# EEZ_DIB_AUX_PS_r3B2.net
KiCad netlist of a schematic drawn in EAGLE
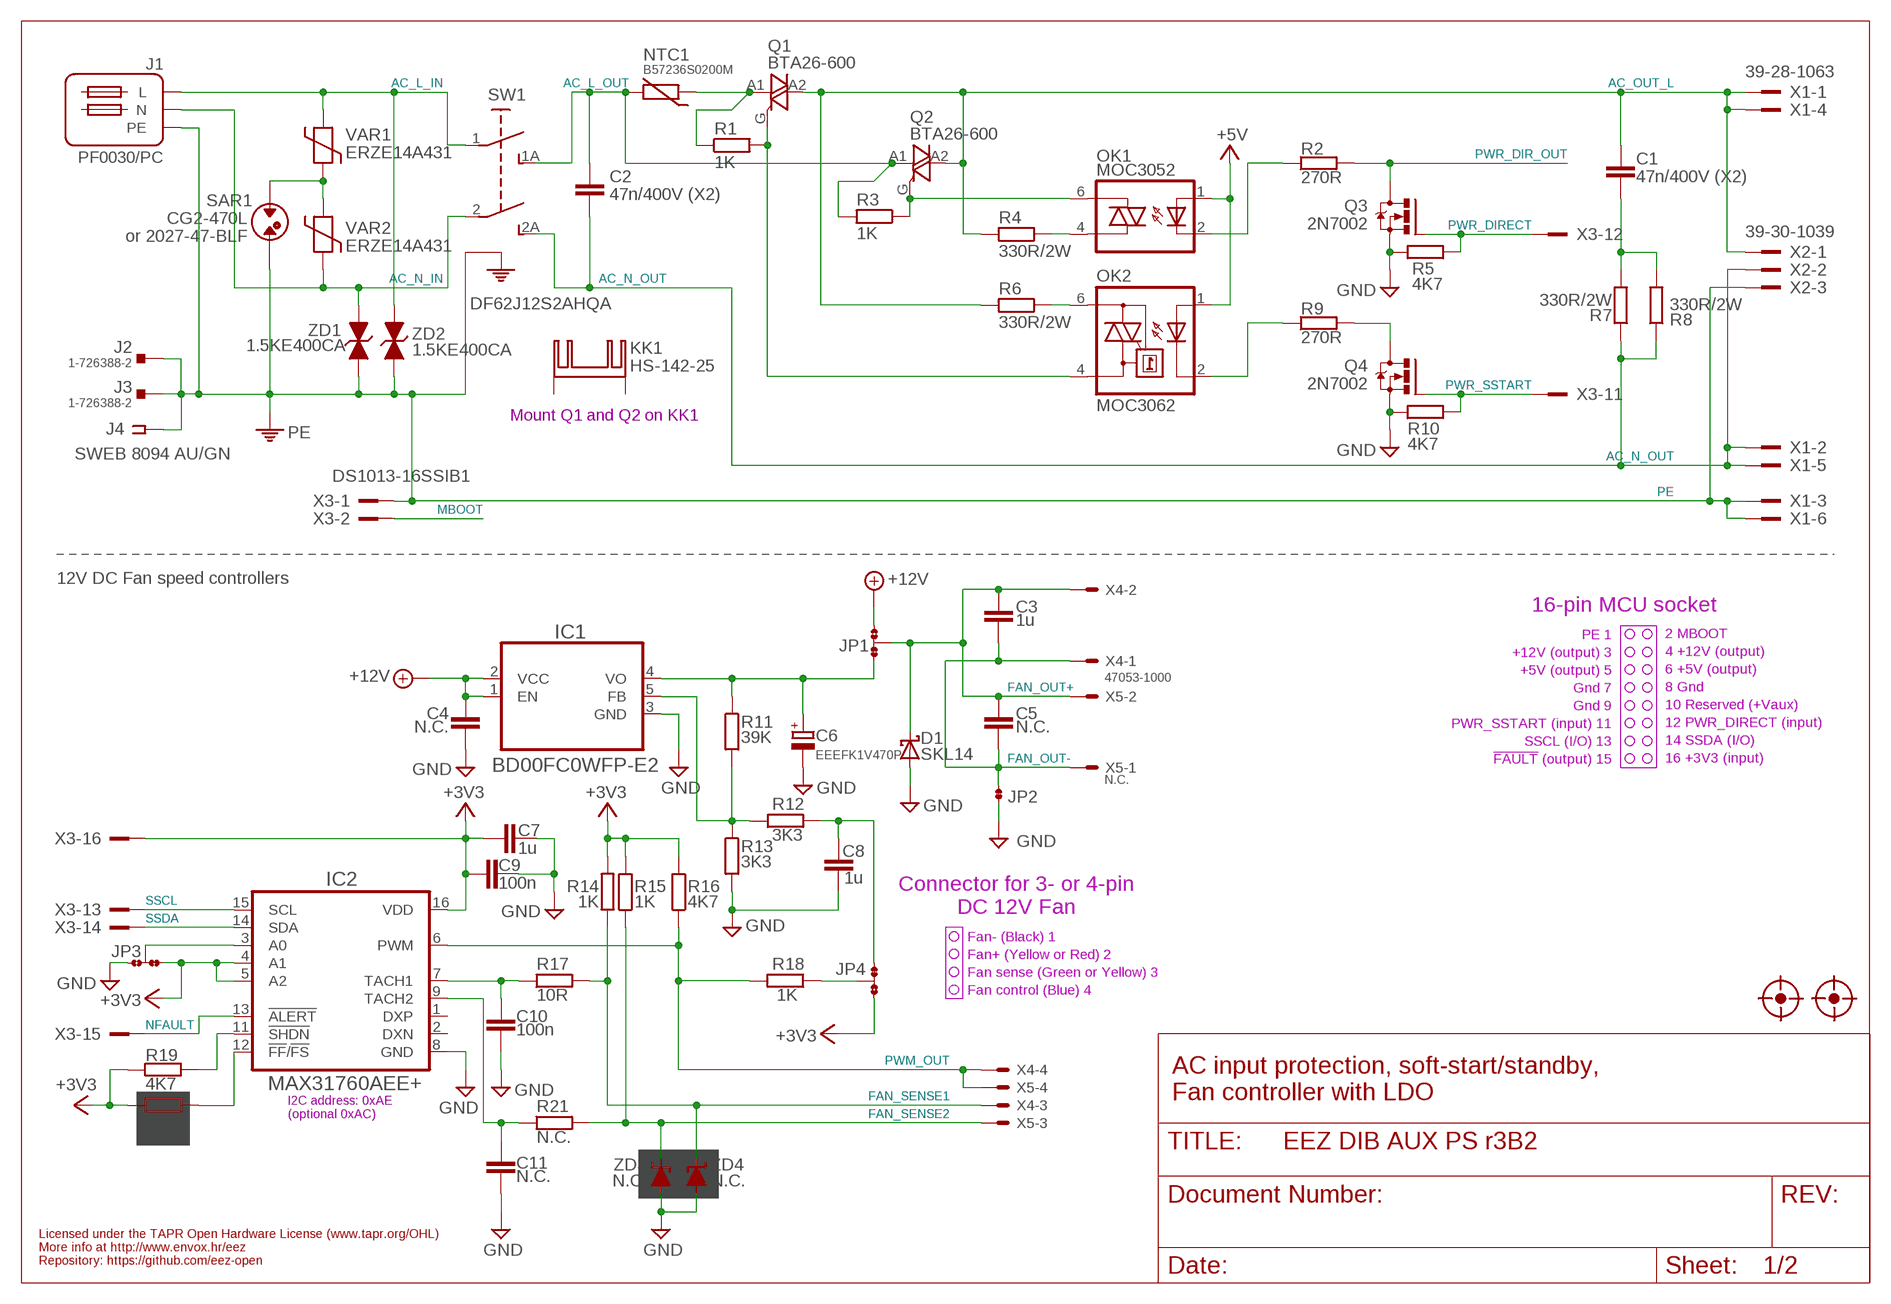
[diagram p0: schematic, sheet 1]
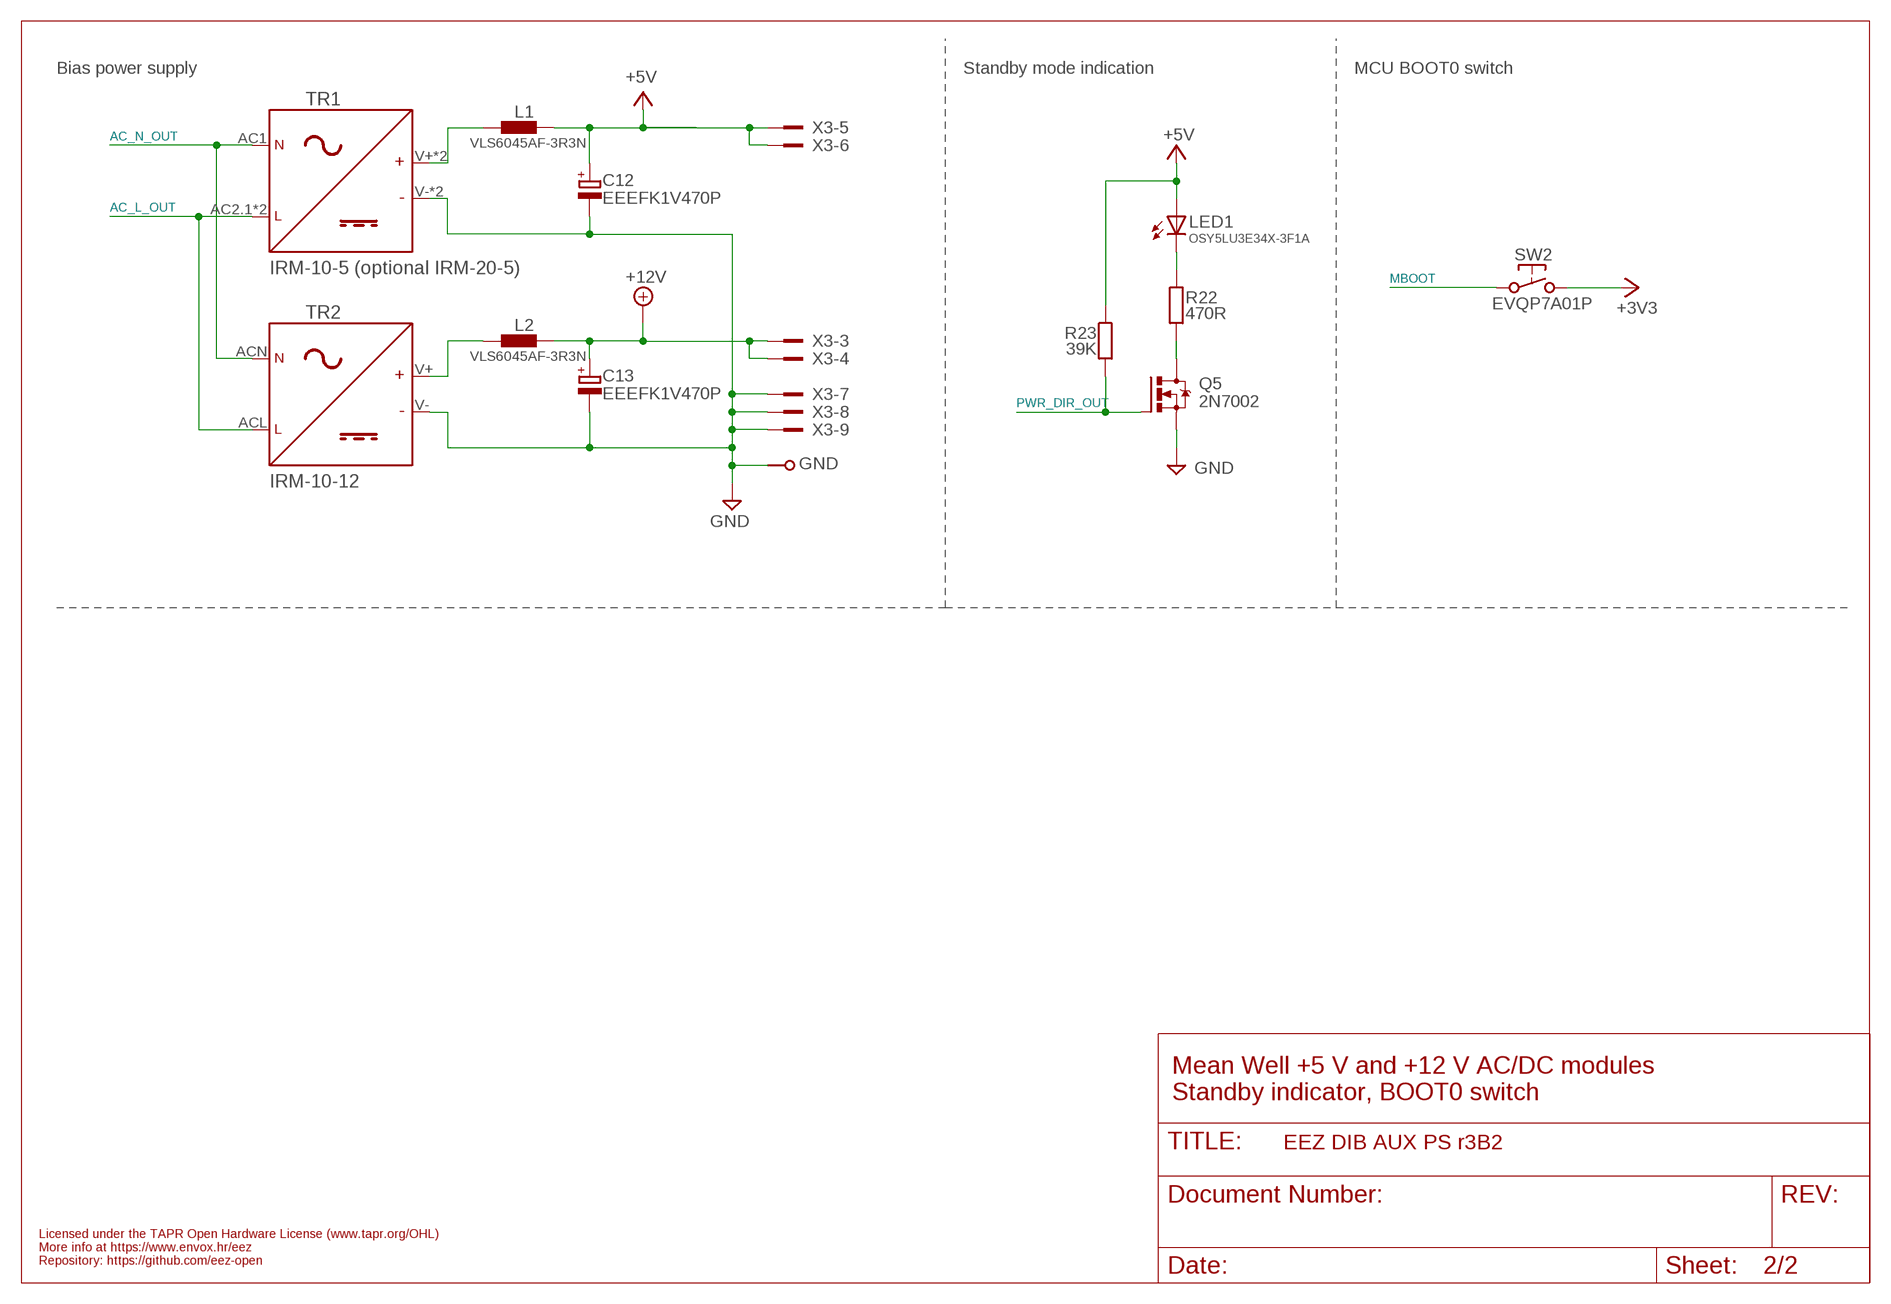
[diagram p1: schematic, sheet 2]

(export (version "E")
  (design (tool "Eeschema 10.0.6"))
  (components
    (comp (ref "C12")
      (value "EEEFK1V470P")
      (footprint "eagle-import:CAPAE660X610N")
      (libsource (lib "eagle-import") (part "ECAPPANASONIC_H"))
    )
    (comp (ref "C13")
      (value "EEEFK1V470P")
      (footprint "eagle-import:CAPAE660X610N")
      (libsource (lib "eagle-import") (part "ECAPPANASONIC_H"))
    )
    (comp (ref "GND")
      (value "PCB_TEST_TABSHIELD")
      (footprint "eagle-import:PCB_SHIELD_TAB")
      (libsource (lib "eagle-import") (part "PCB_TEST_TABSHIELD"))
    )
    (comp (ref "L1")
      (value "VLS6045AF-3R3N")
      (footprint "eagle-import:COILCRAFT_HPI0630")
      (libsource (lib "eagle-import") (part "COILCRAFT_HPI0630"))
    )
    (comp (ref "L2")
      (value "VLS6045AF-3R3N")
      (footprint "eagle-import:COILCRAFT_HPI0630")
      (libsource (lib "eagle-import") (part "COILCRAFT_HPI0630"))
    )
    (comp (ref "LED1")
      (value "OSY5LU3E34X-3F1A")
      (footprint "eagle-import:OSG8")
      (libsource (lib "eagle-import") (part "LEDOSG8"))
    )
    (comp (ref "Q5")
      (value "2N7002")
      (footprint "eagle-import:SOT103P240X110-3N")
      (fields
        (field (name "MPN") "2N7002-7-F")
        (field (name "MPN_1") "2N7002-7-F")
        (field (name "OC_FARNELL") "1713823")
        (field (name "OC_NEWARK") "25R5679")
        (field (name "PACKAGE") "SOT-23-3")
        (field (name "SUPPLIER") "DIODES INC.")
      )
      (libsource (lib "eagle-import") (part "2N7002"))
    )
    (comp (ref "R22")
      (value "470R")
      (footprint "eagle-import:R0805")
      (libsource (lib "eagle-import") (part "R-EU_R0805"))
    )
    (comp (ref "R23")
      (value "39K")
      (footprint "eagle-import:R0805")
      (libsource (lib "eagle-import") (part "R-EU_R0805"))
    )
    (comp (ref "SW2")
      (value "EVQP7A01P")
      (footprint "eagle-import:PANASONIC_EVQP")
      (libsource (lib "eagle-import") (part "EVQP7A01P"))
    )
    (comp (ref "TR1")
      (value "IRM-10-5 (optional IRM-20-5)")
      (footprint "eagle-import:IRM-10_20_COMBO")
      (libsource (lib "eagle-import") (part "AC_DC_ADAPTERIRM10/20"))
    )
    (comp (ref "TR2")
      (value "IRM-10-12")
      (footprint "eagle-import:IRM-10")
      (libsource (lib "eagle-import") (part "AC_DC_ADAPTERIRM10"))
    )
    (comp (ref "X3")
      (value "DS1013-16SSIB1")
      (footprint "eagle-import:IDC-16PIN")
      (libsource (lib "eagle-import") (part "IDC-16PIN"))
    )
    (comp (ref "C1")
      (value "47n/400V (X2)")
      (footprint "eagle-import:C102-054X133")
      (libsource (lib "eagle-import") (part "C-EU102-054X133"))
    )
    (comp (ref "C2")
      (value "47n/400V (X2)")
      (footprint "eagle-import:C102-054X133")
      (libsource (lib "eagle-import") (part "C-EU102-054X133"))
    )
    (comp (ref "C3")
      (value "1u")
      (footprint "eagle-import:C0805")
      (libsource (lib "eagle-import") (part "C-EUC0805"))
    )
    (comp (ref "C4")
      (value "N.C.")
      (footprint "eagle-import:C0805")
      (libsource (lib "eagle-import") (part "C-EUC0805"))
    )
    (comp (ref "C5")
      (value "N.C.")
      (footprint "eagle-import:C0805")
      (libsource (lib "eagle-import") (part "C-EUC0805"))
    )
    (comp (ref "C6")
      (value "EEEFK1V470P")
      (footprint "eagle-import:CAPAE660X610N")
      (libsource (lib "eagle-import") (part "ECAPPANASONIC_H"))
    )
    (comp (ref "C7")
      (value "1u")
      (footprint "eagle-import:C0805")
      (libsource (lib "eagle-import") (part "C-EUC0805"))
    )
    (comp (ref "C8")
      (value "1u")
      (footprint "eagle-import:C0805")
      (libsource (lib "eagle-import") (part "C-EUC0805"))
    )
    (comp (ref "C9")
      (value "100n")
      (footprint "eagle-import:C0603")
      (libsource (lib "eagle-import") (part "C-EUC0603"))
    )
    (comp (ref "C10")
      (value "100n")
      (footprint "eagle-import:C0603")
      (libsource (lib "eagle-import") (part "C-EUC0603"))
    )
    (comp (ref "C11")
      (value "N.C.")
      (footprint "eagle-import:C0603")
      (libsource (lib "eagle-import") (part "C-EUC0603"))
    )
    (comp (ref "D1")
      (value "SKL14")
      (footprint "eagle-import:SOD123")
      (libsource (lib "eagle-import") (part "SCHOTTKYSOD123"))
    )
    (comp (ref "FM1")
      (value "FIDUCIAL")
      (footprint "eagle-import:FIDUCIAL")
      (libsource (lib "eagle-import") (part "FIDUCIAL"))
    )
    (comp (ref "FM2")
      (value "FIDUCIAL")
      (footprint "eagle-import:FIDUCIAL")
      (libsource (lib "eagle-import") (part "FIDUCIAL"))
    )
    (comp (ref "IC1")
      (value "BD00FC0WFP-E2")
      (footprint "eagle-import:TO-252-5")
      (libsource (lib "eagle-import") (part "BD00FC0W"))
    )
    (comp (ref "IC2")
      (value "MAX31760AEE+")
      (footprint "eagle-import:DBQ16")
      (libsource (lib "eagle-import") (part "MAX31760AEE+"))
    )
    (comp (ref "J1")
      (value "PF0030/PC")
      (footprint "eagle-import:PF0030_PC")
      (libsource (lib "eagle-import") (part "PF0030/PC"))
    )
    (comp (ref "J2")
      (value "1-726388-2")
      (footprint "eagle-import:PCB_TAB-4.8MM")
      (libsource (lib "eagle-import") (part "PCB_TAB4.8MM"))
    )
    (comp (ref "J3")
      (value "1-726388-2")
      (footprint "eagle-import:PCB_TAB-4.8MM")
      (libsource (lib "eagle-import") (part "PCB_TAB4.8MM"))
    )
    (comp (ref "J4")
      (value "SWEB 8094 AU/GN")
      (footprint "eagle-import:S16N-PC")
      (libsource (lib "eagle-import") (part "BINDING_POSTCLIFF"))
    )
    (comp (ref "JP1")
      (value "JP3-CUT")
      (footprint "eagle-import:JP3-CUT")
      (libsource (lib "eagle-import") (part "JP3-CUT"))
    )
    (comp (ref "JP2")
      (value "JP2-NOCUT")
      (footprint "eagle-import:JP2-NOCUT")
      (libsource (lib "eagle-import") (part "JP2-NOCUT"))
    )
    (comp (ref "JP3")
      (value "JP3-CUT")
      (footprint "eagle-import:JP3-CUT")
      (libsource (lib "eagle-import") (part "JP3-CUT"))
    )
    (comp (ref "JP4")
      (value "JP3-CUT")
      (footprint "eagle-import:JP3-CUT")
      (libsource (lib "eagle-import") (part "JP3-CUT"))
    )
    (comp (ref "KK1")
      (value "HS-142-25")
      (footprint "eagle-import:SK129")
      (libsource (lib "eagle-import") (part "SK129-PAD"))
    )
    (comp (ref "NTC1")
      (value "B57236S0200M")
      (footprint "eagle-import:NTC_11.5X6_RM5")
      (libsource (lib "eagle-import") (part "NTC11.5X6"))
    )
    (comp (ref "OK1")
      (value "MOC3052")
      (footprint "eagle-import:DIL6-SMD")
      (libsource (lib "eagle-import") (part "MOC305X"))
    )
    (comp (ref "OK2")
      (value "MOC3062")
      (footprint "eagle-import:DIL6-SMD")
      (fields
        (field (name "MF") "FAIRCHILD SEMICONDUCTOR")
        (field (name "MPN") "MOC3033S-M")
        (field (name "MF_1") "FAIRCHILD SEMICONDUCTOR")
        (field (name "MPN_1") "MOC3033S-M")
        (field (name "OC_FARNELL") "unknown")
        (field (name "OC_NEWARK") "05C2878")
      )
      (libsource (lib "eagle-import") (part "MOC30S33"))
    )
    (comp (ref "Q1")
      (value "BTA26-600")
      (footprint "eagle-import:TOP3S-1")
      (libsource (lib "eagle-import") (part "BTA26-V"))
    )
    (comp (ref "Q2")
      (value "BTA26-600")
      (footprint "eagle-import:TOP3S-1")
      (libsource (lib "eagle-import") (part "BTA26-V"))
    )
    (comp (ref "Q3")
      (value "2N7002")
      (footprint "eagle-import:SOT103P240X110-3N")
      (fields (field (name "MPN") "2N7002-7-F"))
      (libsource (lib "eagle-import") (part "2N7002"))
    )
    (comp (ref "Q4")
      (value "2N7002")
      (footprint "eagle-import:SOT103P240X110-3N")
      (fields (field (name "MPN") "2N7002-7-F"))
      (libsource (lib "eagle-import") (part "2N7002"))
    )
    (comp (ref "R1")
      (value "1K")
      (footprint "eagle-import:R0805")
      (libsource (lib "eagle-import") (part "R-EU_R0805"))
    )
    (comp (ref "R2")
      (value "270R")
      (footprint "eagle-import:R0805")
      (libsource (lib "eagle-import") (part "R-EU_R0805"))
    )
    (comp (ref "R3")
      (value "1K")
      (footprint "eagle-import:R0805")
      (libsource (lib "eagle-import") (part "R-EU_R0805"))
    )
    (comp (ref "R4")
      (value "330R/2W")
      (footprint "eagle-import:R2512")
      (libsource (lib "eagle-import") (part "R-EU_R2512"))
    )
    (comp (ref "R5")
      (value "4K7")
      (footprint "eagle-import:R0805")
      (libsource (lib "eagle-import") (part "R-EU_R0805"))
    )
    (comp (ref "R6")
      (value "330R/2W")
      (footprint "eagle-import:R2512")
      (libsource (lib "eagle-import") (part "R-EU_R2512"))
    )
    (comp (ref "R7")
      (value "330R/2W")
      (footprint "eagle-import:R2512")
      (libsource (lib "eagle-import") (part "R-EU_R2512"))
    )
    (comp (ref "R8")
      (value "330R/2W")
      (footprint "eagle-import:R2512")
      (libsource (lib "eagle-import") (part "R-EU_R2512"))
    )
    (comp (ref "R9")
      (value "270R")
      (footprint "eagle-import:R0805")
      (libsource (lib "eagle-import") (part "R-EU_R0805"))
    )
    (comp (ref "R10")
      (value "4K7")
      (footprint "eagle-import:R0805")
      (libsource (lib "eagle-import") (part "R-EU_R0805"))
    )
    (comp (ref "R11")
      (value "39K")
      (footprint "eagle-import:R0805")
      (libsource (lib "eagle-import") (part "R-EU_R0805"))
    )
    (comp (ref "R12")
      (value "3K3")
      (footprint "eagle-import:R0805")
      (libsource (lib "eagle-import") (part "R-EU_R0805"))
    )
    (comp (ref "R13")
      (value "3K3")
      (footprint "eagle-import:R0805")
      (libsource (lib "eagle-import") (part "R-EU_R0805"))
    )
    (comp (ref "R14")
      (value "1K")
      (footprint "eagle-import:R0805")
      (libsource (lib "eagle-import") (part "R-EU_R0805"))
    )
    (comp (ref "R15")
      (value "1K")
      (footprint "eagle-import:R0805")
      (libsource (lib "eagle-import") (part "R-EU_R0805"))
    )
    (comp (ref "R16")
      (value "4K7")
      (footprint "eagle-import:R0805")
      (libsource (lib "eagle-import") (part "R-EU_R0805"))
    )
    (comp (ref "R17")
      (value "10R")
      (footprint "eagle-import:R0805")
      (libsource (lib "eagle-import") (part "R-EU_R0805"))
    )
    (comp (ref "R18")
      (value "1K")
      (footprint "eagle-import:R0805")
      (libsource (lib "eagle-import") (part "R-EU_R0805"))
    )
    (comp (ref "R19")
      (value "4K7")
      (footprint "eagle-import:R0805")
      (libsource (lib "eagle-import") (part "R-EU_R0805"))
    )
    (comp (ref "R20")
      (value "N.C.")
      (footprint "eagle-import:R0805")
      (libsource (lib "eagle-import") (part "R-EU_R0805"))
    )
    (comp (ref "R21")
      (value "N.C.")
      (footprint "eagle-import:R0805")
      (libsource (lib "eagle-import") (part "R-EU_R0805"))
    )
    (comp (ref "SAR1")
      (value "CG2-470L")
      (footprint "eagle-import:SAR")
      (libsource (lib "eagle-import") (part "SAR"))
    )
    (comp (ref "SW1")
      (value "DF62J12S2AHQA")
      (footprint "eagle-import:DF62J12S2")
      (libsource (lib "eagle-import") (part "DF62J12S2AHQA"))
    )
    (comp (ref "VAR1")
      (value "ERZE14A431")
      (footprint "eagle-import:VARISTOR_13MM")
      (libsource (lib "eagle-import") (part "VARISTOR-13"))
    )
    (comp (ref "VAR2")
      (value "ERZE14A431")
      (footprint "eagle-import:VARISTOR_13MM")
      (libsource (lib "eagle-import") (part "VARISTOR-13"))
    )
    (comp (ref "X1")
      (value "39-28-1063")
      (footprint "eagle-import:MINIFIT_5566-06A_CRE")
      (libsource (lib "eagle-import") (part "MINIFIT_5566-06A-CRE"))
    )
    (comp (ref "X2")
      (value "39-30-1039")
      (footprint "eagle-import:MINIFIT_39301039_CRE")
      (libsource (lib "eagle-import") (part "MINIFIT_39301039-CREEPAGE"))
    )
    (comp (ref "X4")
      (value "47053-1000")
      (footprint "eagle-import:47053-1000")
      (libsource (lib "eagle-import") (part "47053-1000"))
    )
    (comp (ref "X5")
      (value "N.C.")
      (footprint "eagle-import:47053-1000")
      (libsource (lib "eagle-import") (part "47053-1000"))
    )
    (comp (ref "ZD1")
      (value "1.5KE400CA")
      (footprint "eagle-import:DO201-BIDIR")
      (libsource (lib "eagle-import") (part "1.5KE-BIDIR"))
    )
    (comp (ref "ZD2")
      (value "1.5KE400CA")
      (footprint "eagle-import:DO201-BIDIR")
      (libsource (lib "eagle-import") (part "1.5KE-BIDIR"))
    )
    (comp (ref "ZD3")
      (value "N.C.")
      (footprint "eagle-import:SOD123")
      (libsource (lib "eagle-import") (part "ZENER-DIODESOD123"))
    )
    (comp (ref "ZD4")
      (value "N.C.")
      (footprint "eagle-import:SOD123")
      (libsource (lib "eagle-import") (part "ZENER-DIODESOD123"))
    )
  )
  (nets
    (net (code "1") (name "+3V3") (class "Default")
      (node (ref "C7") (pin "2") (pinfunction "2_2") (pintype "passive"))
      (node (ref "C9") (pin "2") (pinfunction "2_2") (pintype "passive"))
      (node (ref "IC2") (pin "16") (pinfunction "VDD_16") (pintype "power_in"))
      (node (ref "IC2") (pin "4") (pinfunction "A1_4") (pintype "input"))
      (node (ref "IC2") (pin "5") (pinfunction "A2_5") (pintype "input"))
      (node (ref "JP3") (pin "NC") (pinfunction "NC_NC") (pintype "passive"))
      (node (ref "JP4") (pin "NO") (pinfunction "NO_NO") (pintype "passive"))
      (node (ref "R14") (pin "2") (pinfunction "2_2") (pintype "passive"))
      (node (ref "R15") (pin "2") (pinfunction "2_2") (pintype "passive"))
      (node (ref "R16") (pin "2") (pinfunction "2_2") (pintype "passive"))
      (node (ref "R19") (pin "2") (pinfunction "2_2") (pintype "passive"))
      (node (ref "R20") (pin "2") (pinfunction "2_2") (pintype "passive"))
      (node (ref "SW2") (pin "2.1") (pinfunction "2_2.1") (pintype "passive"))
      (node (ref "SW2") (pin "2.2") (pinfunction "2_2.2") (pintype "passive"))
      (node (ref "X3") (pin "16") (pinfunction "1_16") (pintype "passive"))
    )
    (net (code "2") (name "+5V") (class "Default")
      (node (ref "C12") (pin "1") (pinfunction "+_1") (pintype "passive"))
      (node (ref "L1") (pin "2") (pinfunction "2_2") (pintype "passive"))
      (node (ref "LED1") (pin "A") (pinfunction "A_A") (pintype "passive"))
      (node (ref "OK1") (pin "1") (pinfunction "A_1") (pintype "passive"))
      (node (ref "OK2") (pin "1") (pinfunction "A_1") (pintype "passive"))
      (node (ref "R23") (pin "1") (pinfunction "1_1") (pintype "passive"))
      (node (ref "X3") (pin "5") (pinfunction "1_5") (pintype "passive"))
      (node (ref "X3") (pin "6") (pinfunction "1_6") (pintype "passive"))
    )
    (net (code "3") (name "+12V") (class "Default")
      (node (ref "C13") (pin "1") (pinfunction "+_1") (pintype "passive"))
      (node (ref "C4") (pin "1") (pinfunction "1_1") (pintype "passive"))
      (node (ref "IC1") (pin "1") (pinfunction "EN_1") (pintype "passive"))
      (node (ref "IC1") (pin "2") (pinfunction "VCC_2") (pintype "passive"))
      (node (ref "JP1") (pin "NO") (pinfunction "NO_NO") (pintype "passive"))
      (node (ref "L2") (pin "2") (pinfunction "2_2") (pintype "passive"))
      (node (ref "X3") (pin "3") (pinfunction "1_3") (pintype "passive"))
      (node (ref "X3") (pin "4") (pinfunction "1_4") (pintype "passive"))
    )
    (net (code "4") (name "AC_L_IN") (class "Default")
      (node (ref "J1") (pin "L") (pinfunction "L_L") (pintype "bidirectional"))
      (node (ref "SW1") (pin "1") (pinfunction "P_1") (pintype "passive"))
      (node (ref "VAR1") (pin "2") (pinfunction "P$2_2") (pintype "bidirectional"))
      (node (ref "ZD2") (pin "A") (pinfunction "2_A") (pintype "passive"))
    )
    (net (code "5") (name "AC_L_OUT") (class "Default")
      (node (ref "C2") (pin "1") (pinfunction "1_1") (pintype "passive"))
      (node (ref "NTC1") (pin "1") (pinfunction "P$1_1") (pintype "bidirectional"))
      (node (ref "Q2") (pin "A1") (pinfunction "A1_A1") (pintype "passive"))
      (node (ref "R3") (pin "2") (pinfunction "2_2") (pintype "passive"))
      (node (ref "SW1") (pin "1A") (pinfunction "S_1A") (pintype "passive"))
      (node (ref "TR1") (pin "AC2.1") (pinfunction "AC/L_AC2.1") (pintype "input"))
      (node (ref "TR1") (pin "AC2.2") (pinfunction "AC/L_AC2.2") (pintype "input"))
      (node (ref "TR2") (pin "ACL") (pinfunction "AC/L_ACL") (pintype "input"))
    )
    (net (code "6") (name "AC_N_IN") (class "Default")
      (node (ref "J1") (pin "N") (pinfunction "N_N") (pintype "bidirectional"))
      (node (ref "SW1") (pin "2") (pinfunction "P1_2") (pintype "passive"))
      (node (ref "VAR2") (pin "1") (pinfunction "P$1_1") (pintype "bidirectional"))
      (node (ref "ZD1") (pin "A") (pinfunction "2_A") (pintype "passive"))
    )
    (net (code "7") (name "AC_N_OUT") (class "Default")
      (node (ref "C2") (pin "2") (pinfunction "2_2") (pintype "passive"))
      (node (ref "R7") (pin "1") (pinfunction "1_1") (pintype "passive"))
      (node (ref "R8") (pin "1") (pinfunction "1_1") (pintype "passive"))
      (node (ref "SW1") (pin "2A") (pinfunction "S1_2A") (pintype "passive"))
      (node (ref "TR1") (pin "AC1") (pinfunction "AC/N_AC1") (pintype "input"))
      (node (ref "TR2") (pin "ACN") (pinfunction "AC/N_ACN") (pintype "input"))
      (node (ref "X1") (pin "2") (pinfunction "1_2") (pintype "passive"))
      (node (ref "X1") (pin "5") (pinfunction "1_5") (pintype "passive"))
      (node (ref "X2") (pin "2") (pinfunction "1_2") (pintype "passive"))
    )
    (net (code "8") (name "AC_OUT_L") (class "Default")
      (node (ref "C1") (pin "1") (pinfunction "1_1") (pintype "passive"))
      (node (ref "Q1") (pin "A2") (pinfunction "A2_A2") (pintype "passive"))
      (node (ref "Q2") (pin "A2") (pinfunction "A2_A2") (pintype "passive"))
      (node (ref "R4") (pin "2") (pinfunction "2_2") (pintype "passive"))
      (node (ref "R6") (pin "2") (pinfunction "2_2") (pintype "passive"))
      (node (ref "X1") (pin "1") (pinfunction "1_1") (pintype "passive"))
      (node (ref "X1") (pin "4") (pinfunction "1_4") (pintype "passive"))
      (node (ref "X2") (pin "1") (pinfunction "1_1") (pintype "passive"))
    )
    (net (code "9") (name "FAN_OUT+") (class "Default")
      (node (ref "C3") (pin "1") (pinfunction "1_1") (pintype "passive"))
      (node (ref "C5") (pin "1") (pinfunction "1_1") (pintype "passive"))
      (node (ref "D1") (pin "C") (pinfunction "C_C") (pintype "passive"))
      (node (ref "JP1") (pin "COM") (pinfunction "COM_COM") (pintype "passive"))
      (node (ref "X4") (pin "2") (pinfunction "S_2") (pintype "passive"))
      (node (ref "X5") (pin "2") (pinfunction "S_2") (pintype "passive"))
    )
    (net (code "10") (name "FAN_OUT-") (class "Default")
      (node (ref "C3") (pin "2") (pinfunction "2_2") (pintype "passive"))
      (node (ref "C5") (pin "2") (pinfunction "2_2") (pintype "passive"))
      (node (ref "JP2") (pin "2") (pinfunction "2_2") (pintype "passive"))
      (node (ref "X4") (pin "1") (pinfunction "S_1") (pintype "passive"))
      (node (ref "X5") (pin "1") (pinfunction "S_1") (pintype "passive"))
    )
    (net (code "11") (name "FAN_SENSE1") (class "Default")
      (node (ref "R14") (pin "1") (pinfunction "1_1") (pintype "passive"))
      (node (ref "R17") (pin "2") (pinfunction "2_2") (pintype "passive"))
      (node (ref "X4") (pin "3") (pinfunction "S_3") (pintype "passive"))
      (node (ref "ZD4") (pin "C") (pinfunction "C_C") (pintype "passive"))
    )
    (net (code "12") (name "FAN_SENSE2") (class "Default")
      (node (ref "R15") (pin "1") (pinfunction "1_1") (pintype "passive"))
      (node (ref "R21") (pin "2") (pinfunction "2_2") (pintype "passive"))
      (node (ref "X5") (pin "3") (pinfunction "S_3") (pintype "passive"))
      (node (ref "ZD3") (pin "C") (pinfunction "C_C") (pintype "passive"))
    )
    (net (code "13") (name "GND") (class "Default")
      (node (ref "C10") (pin "2") (pinfunction "2_2") (pintype "passive"))
      (node (ref "C11") (pin "2") (pinfunction "2_2") (pintype "passive"))
      (node (ref "C12") (pin "2") (pinfunction "-_2") (pintype "passive"))
      (node (ref "C13") (pin "2") (pinfunction "-_2") (pintype "passive"))
      (node (ref "C4") (pin "2") (pinfunction "2_2") (pintype "passive"))
      (node (ref "C6") (pin "2") (pinfunction "-_2") (pintype "passive"))
      (node (ref "C7") (pin "1") (pinfunction "1_1") (pintype "passive"))
      (node (ref "C8") (pin "2") (pinfunction "2_2") (pintype "passive"))
      (node (ref "C9") (pin "1") (pinfunction "1_1") (pintype "passive"))
      (node (ref "D1") (pin "A") (pinfunction "A_A") (pintype "passive"))
      (node (ref "GND") (pin "1") (pinfunction "P$1_1") (pintype "bidirectional"))
      (node (ref "IC1") (pin "3") (pinfunction "GND_3") (pintype "passive"))
      (node (ref "IC2") (pin "8") (pinfunction "GND_8") (pintype "power_in"))
      (node (ref "JP2") (pin "1") (pinfunction "1_1") (pintype "passive"))
      (node (ref "JP3") (pin "NO") (pinfunction "NO_NO") (pintype "passive"))
      (node (ref "Q3") (pin "2") (pinfunction "S_2") (pintype "passive"))
      (node (ref "Q4") (pin "2") (pinfunction "S_2") (pintype "passive"))
      (node (ref "Q5") (pin "2") (pinfunction "S_2") (pintype "passive"))
      (node (ref "R10") (pin "1") (pinfunction "1_1") (pintype "passive"))
      (node (ref "R13") (pin "2") (pinfunction "2_2") (pintype "passive"))
      (node (ref "R5") (pin "1") (pinfunction "1_1") (pintype "passive"))
      (node (ref "TR1") (pin "V-") (pinfunction "-_V-") (pintype "passive"))
      (node (ref "TR1") (pin "V-1") (pinfunction "-_V-1") (pintype "passive"))
      (node (ref "TR2") (pin "V-") (pinfunction "-_V-") (pintype "passive"))
      (node (ref "X3") (pin "7") (pinfunction "1_7") (pintype "passive"))
      (node (ref "X3") (pin "8") (pinfunction "1_8") (pintype "passive"))
      (node (ref "X3") (pin "9") (pinfunction "1_9") (pintype "passive"))
      (node (ref "ZD3") (pin "A") (pinfunction "A_A") (pintype "passive"))
      (node (ref "ZD4") (pin "A") (pinfunction "A_A") (pintype "passive"))
    )
    (net (code "14") (name "MBOOT") (class "Default")
      (node (ref "SW2") (pin "1.1") (pinfunction "1_1.1") (pintype "passive"))
      (node (ref "SW2") (pin "1.2") (pinfunction "1_1.2") (pintype "passive"))
      (node (ref "X3") (pin "2") (pinfunction "1_2") (pintype "passive"))
    )
    (net (code "15") (name "NFAULT") (class "Default")
      (node (ref "IC2") (pin "13") (pinfunction "~{ALERT}_13") (pintype "output"))
      (node (ref "X3") (pin "15") (pinfunction "1_15") (pintype "passive"))
    )
    (net (code "16") (name "Net-(C1-Pad2)") (class "Default")
      (node (ref "C1") (pin "2") (pinfunction "2_2") (pintype "passive"))
      (node (ref "R7") (pin "2") (pinfunction "2_2") (pintype "passive"))
      (node (ref "R8") (pin "2") (pinfunction "2_2") (pintype "passive"))
    )
    (net (code "17") (name "Net-(C6-+)") (class "Default")
      (node (ref "C6") (pin "1") (pinfunction "+_1") (pintype "passive"))
      (node (ref "IC1") (pin "4") (pinfunction "VO_4") (pintype "output"))
      (node (ref "JP1") (pin "NC") (pinfunction "NC_NC") (pintype "passive"))
      (node (ref "R11") (pin "1") (pinfunction "1_1") (pintype "passive"))
    )
    (net (code "18") (name "Net-(C8-Pad1)") (class "Default")
      (node (ref "C8") (pin "1") (pinfunction "1_1") (pintype "passive"))
      (node (ref "JP4") (pin "NC") (pinfunction "NC_NC") (pintype "passive"))
      (node (ref "R12") (pin "2") (pinfunction "2_2") (pintype "passive"))
    )
    (net (code "19") (name "Net-(IC1-FB)") (class "Default")
      (node (ref "IC1") (pin "5") (pinfunction "FB_5") (pintype "passive"))
      (node (ref "R11") (pin "2") (pinfunction "2_2") (pintype "passive"))
      (node (ref "R12") (pin "1") (pinfunction "1_1") (pintype "passive"))
      (node (ref "R13") (pin "1") (pinfunction "1_1") (pintype "passive"))
    )
    (net (code "20") (name "Net-(IC2-A0)") (class "Default")
      (node (ref "IC2") (pin "3") (pinfunction "A0_3") (pintype "input"))
      (node (ref "JP3") (pin "COM") (pinfunction "COM_COM") (pintype "passive"))
    )
    (net (code "21") (name "Net-(IC2-TACH1)") (class "Default")
      (node (ref "C10") (pin "1") (pinfunction "1_1") (pintype "passive"))
      (node (ref "IC2") (pin "7") (pinfunction "TACH1_7") (pintype "input"))
      (node (ref "R17") (pin "1") (pinfunction "1_1") (pintype "passive"))
    )
    (net (code "22") (name "Net-(IC2-TACH2)") (class "Default")
      (node (ref "C11") (pin "1") (pinfunction "1_1") (pintype "passive"))
      (node (ref "IC2") (pin "9") (pinfunction "TACH2_9") (pintype "input"))
      (node (ref "R21") (pin "1") (pinfunction "1_1") (pintype "passive"))
    )
    (net (code "23") (name "Net-(IC2-~{FF}{slash}~{FS})") (class "Default")
      (node (ref "IC2") (pin "12") (pinfunction "~{FF}/~{FS}_12") (pintype "bidirectional"))
      (node (ref "R20") (pin "1") (pinfunction "1_1") (pintype "passive"))
    )
    (net (code "24") (name "Net-(IC2-~{SHDN})") (class "Default")
      (node (ref "IC2") (pin "11") (pinfunction "~{SHDN}_11") (pintype "output"))
      (node (ref "R19") (pin "1") (pinfunction "1_1") (pintype "passive"))
    )
    (net (code "25") (name "Net-(JP4-PadCOM)") (class "Default")
      (node (ref "JP4") (pin "COM") (pinfunction "COM_COM") (pintype "passive"))
      (node (ref "R18") (pin "1") (pinfunction "1_1") (pintype "passive"))
    )
    (net (code "26") (name "Net-(L1-Pad1)") (class "Default")
      (node (ref "L1") (pin "1") (pinfunction "1_1") (pintype "passive"))
      (node (ref "TR1") (pin "V+") (pinfunction "+_V+") (pintype "passive"))
      (node (ref "TR1") (pin "V+1") (pinfunction "+_V+1") (pintype "passive"))
    )
    (net (code "27") (name "Net-(LED1-PadC)") (class "Default")
      (node (ref "LED1") (pin "C") (pinfunction "C_C") (pintype "passive"))
      (node (ref "R22") (pin "1") (pinfunction "1_1") (pintype "passive"))
    )
    (net (code "28") (name "Net-(NTC1-P$2)") (class "Default")
      (node (ref "NTC1") (pin "2") (pinfunction "P$2_2") (pintype "bidirectional"))
      (node (ref "Q1") (pin "A1") (pinfunction "A1_A1") (pintype "passive"))
      (node (ref "R1") (pin "1") (pinfunction "1_1") (pintype "passive"))
    )
    (net (code "29") (name "Net-(OK1-A1)") (class "Default")
      (node (ref "OK1") (pin "4") (pinfunction "A1_4") (pintype "passive"))
      (node (ref "R4") (pin "1") (pinfunction "1_1") (pintype "passive"))
    )
    (net (code "30") (name "Net-(OK1-A2)") (class "Default")
      (node (ref "OK1") (pin "6") (pinfunction "A2_6") (pintype "passive"))
      (node (ref "Q2") (pin "G") (pinfunction "G_G") (pintype "passive"))
      (node (ref "R3") (pin "1") (pinfunction "1_1") (pintype "passive"))
    )
    (net (code "31") (name "Net-(OK1-C)") (class "Default")
      (node (ref "OK1") (pin "2") (pinfunction "C_2") (pintype "passive"))
      (node (ref "R2") (pin "1") (pinfunction "1_1") (pintype "passive"))
    )
    (net (code "32") (name "Net-(OK2-A1)") (class "Default")
      (node (ref "OK2") (pin "4") (pinfunction "A1_4") (pintype "passive"))
      (node (ref "Q1") (pin "G") (pinfunction "G_G") (pintype "passive"))
      (node (ref "R1") (pin "2") (pinfunction "2_2") (pintype "passive"))
    )
    (net (code "33") (name "Net-(OK2-A2)") (class "Default")
      (node (ref "OK2") (pin "6") (pinfunction "A2_6") (pintype "passive"))
      (node (ref "R6") (pin "1") (pinfunction "1_1") (pintype "passive"))
    )
    (net (code "34") (name "Net-(OK2-C)") (class "Default")
      (node (ref "OK2") (pin "2") (pinfunction "C_2") (pintype "passive"))
      (node (ref "R9") (pin "1") (pinfunction "1_1") (pintype "passive"))
    )
    (net (code "35") (name "Net-(Q4-D)") (class "Default")
      (node (ref "Q4") (pin "3") (pinfunction "D_3") (pintype "passive"))
      (node (ref "R9") (pin "2") (pinfunction "2_2") (pintype "passive"))
    )
    (net (code "36") (name "Net-(Q5-D)") (class "Default")
      (node (ref "Q5") (pin "3") (pinfunction "D_3") (pintype "passive"))
      (node (ref "R22") (pin "2") (pinfunction "2_2") (pintype "passive"))
    )
    (net (code "37") (name "Net-(TR2-+)") (class "Default")
      (node (ref "L2") (pin "1") (pinfunction "1_1") (pintype "passive"))
      (node (ref "TR2") (pin "V+") (pinfunction "+_V+") (pintype "passive"))
    )
    (net (code "38") (name "Net-(VAR1-P$1)") (class "Default")
      (node (ref "SAR1") (pin "P$1") (pinfunction "P$1_P$1") (pintype "bidirectional"))
      (node (ref "VAR1") (pin "1") (pinfunction "P$1_1") (pintype "bidirectional"))
      (node (ref "VAR2") (pin "2") (pinfunction "P$2_2") (pintype "bidirectional"))
    )
    (net (code "39") (name "PE") (class "Default")
      (node (ref "J1") (pin "PE") (pinfunction "PE_PE") (pintype "bidirectional"))
      (node (ref "J2") (pin "1") (pinfunction "P$1_1") (pintype "bidirectional"))
      (node (ref "J2") (pin "2") (pinfunction "P$1_2") (pintype "bidirectional"))
      (node (ref "J3") (pin "1") (pinfunction "P$1_1") (pintype "bidirectional"))
      (node (ref "J3") (pin "2") (pinfunction "P$1_2") (pintype "bidirectional"))
      (node (ref "J4") (pin "1") (pinfunction "1_1") (pintype "passive"))
      (node (ref "J4") (pin "NC1") (pinfunction "1_NC1") (pintype "passive"))
      (node (ref "J4") (pin "NC2") (pinfunction "1_NC2") (pintype "passive"))
      (node (ref "J4") (pin "NC3") (pinfunction "1_NC3") (pintype "passive"))
      (node (ref "J4") (pin "NC4") (pinfunction "1_NC4") (pintype "passive"))
      (node (ref "SAR1") (pin "P$2") (pinfunction "P$2_P$2") (pintype "bidirectional"))
      (node (ref "SW1") (pin "PE1") (pinfunction "PE_PE1") (pintype "power_in"))
      (node (ref "SW1") (pin "PE2") (pinfunction "PE_PE2") (pintype "power_in"))
      (node (ref "X1") (pin "3") (pinfunction "1_3") (pintype "passive"))
      (node (ref "X1") (pin "6") (pinfunction "1_6") (pintype "passive"))
      (node (ref "X2") (pin "3") (pinfunction "1_3") (pintype "passive"))
      (node (ref "X3") (pin "1") (pinfunction "1_1") (pintype "passive"))
      (node (ref "ZD1") (pin "C") (pinfunction "1_C") (pintype "passive"))
      (node (ref "ZD2") (pin "C") (pinfunction "1_C") (pintype "passive"))
    )
    (net (code "40") (name "PWM_OUT") (class "Default")
      (node (ref "IC2") (pin "6") (pinfunction "PWM_6") (pintype "output"))
      (node (ref "R16") (pin "1") (pinfunction "1_1") (pintype "passive"))
      (node (ref "R18") (pin "2") (pinfunction "2_2") (pintype "passive"))
      (node (ref "X4") (pin "4") (pinfunction "S_4") (pintype "passive"))
      (node (ref "X5") (pin "4") (pinfunction "S_4") (pintype "passive"))
    )
    (net (code "41") (name "PWR_DIRECT") (class "Default")
      (node (ref "Q3") (pin "1") (pinfunction "G_1") (pintype "passive"))
      (node (ref "R5") (pin "2") (pinfunction "2_2") (pintype "passive"))
      (node (ref "X3") (pin "12") (pinfunction "1_12") (pintype "passive"))
    )
    (net (code "42") (name "PWR_DIR_OUT") (class "Default")
      (node (ref "Q3") (pin "3") (pinfunction "D_3") (pintype "passive"))
      (node (ref "Q5") (pin "1") (pinfunction "G_1") (pintype "passive"))
      (node (ref "R2") (pin "2") (pinfunction "2_2") (pintype "passive"))
      (node (ref "R23") (pin "2") (pinfunction "2_2") (pintype "passive"))
    )
    (net (code "43") (name "PWR_SSTART") (class "Default")
      (node (ref "Q4") (pin "1") (pinfunction "G_1") (pintype "passive"))
      (node (ref "R10") (pin "2") (pinfunction "2_2") (pintype "passive"))
      (node (ref "X3") (pin "11") (pinfunction "1_11") (pintype "passive"))
    )
    (net (code "44") (name "SSCL") (class "Default")
      (node (ref "IC2") (pin "15") (pinfunction "SCL_15") (pintype "input"))
      (node (ref "X3") (pin "13") (pinfunction "1_13") (pintype "passive"))
    )
    (net (code "45") (name "SSDA") (class "Default")
      (node (ref "IC2") (pin "14") (pinfunction "SDA_14") (pintype "bidirectional"))
      (node (ref "X3") (pin "14") (pinfunction "1_14") (pintype "passive"))
    )
    (net (code "46") (name "unconnected-(IC2-DXN-Pad2)") (class "Default")
      (node (ref "IC2") (pin "2") (pinfunction "DXN_2") (pintype "input"))
    )
    (net (code "47") (name "unconnected-(IC2-DXP-Pad1)") (class "Default")
      (node (ref "IC2") (pin "1") (pinfunction "DXP_1") (pintype "input"))
    )
    (net (code "48") (name "unconnected-(KK1-K-PadA2,5)") (class "Default")
      (node (ref "KK1") (pin "A2,5") (pinfunction "K_A2,5") (pintype "passive"))
    )
    (net (code "49") (name "unconnected-(KK1-K-PadB2,5)") (class "Default")
      (node (ref "KK1") (pin "B2,5") (pinfunction "K_B2,5") (pintype "passive"))
    )
  )
)
